# SCH_URM07-Test_2025-05-04.net
KiCad netlist of a schematic drawn in EasyEDA
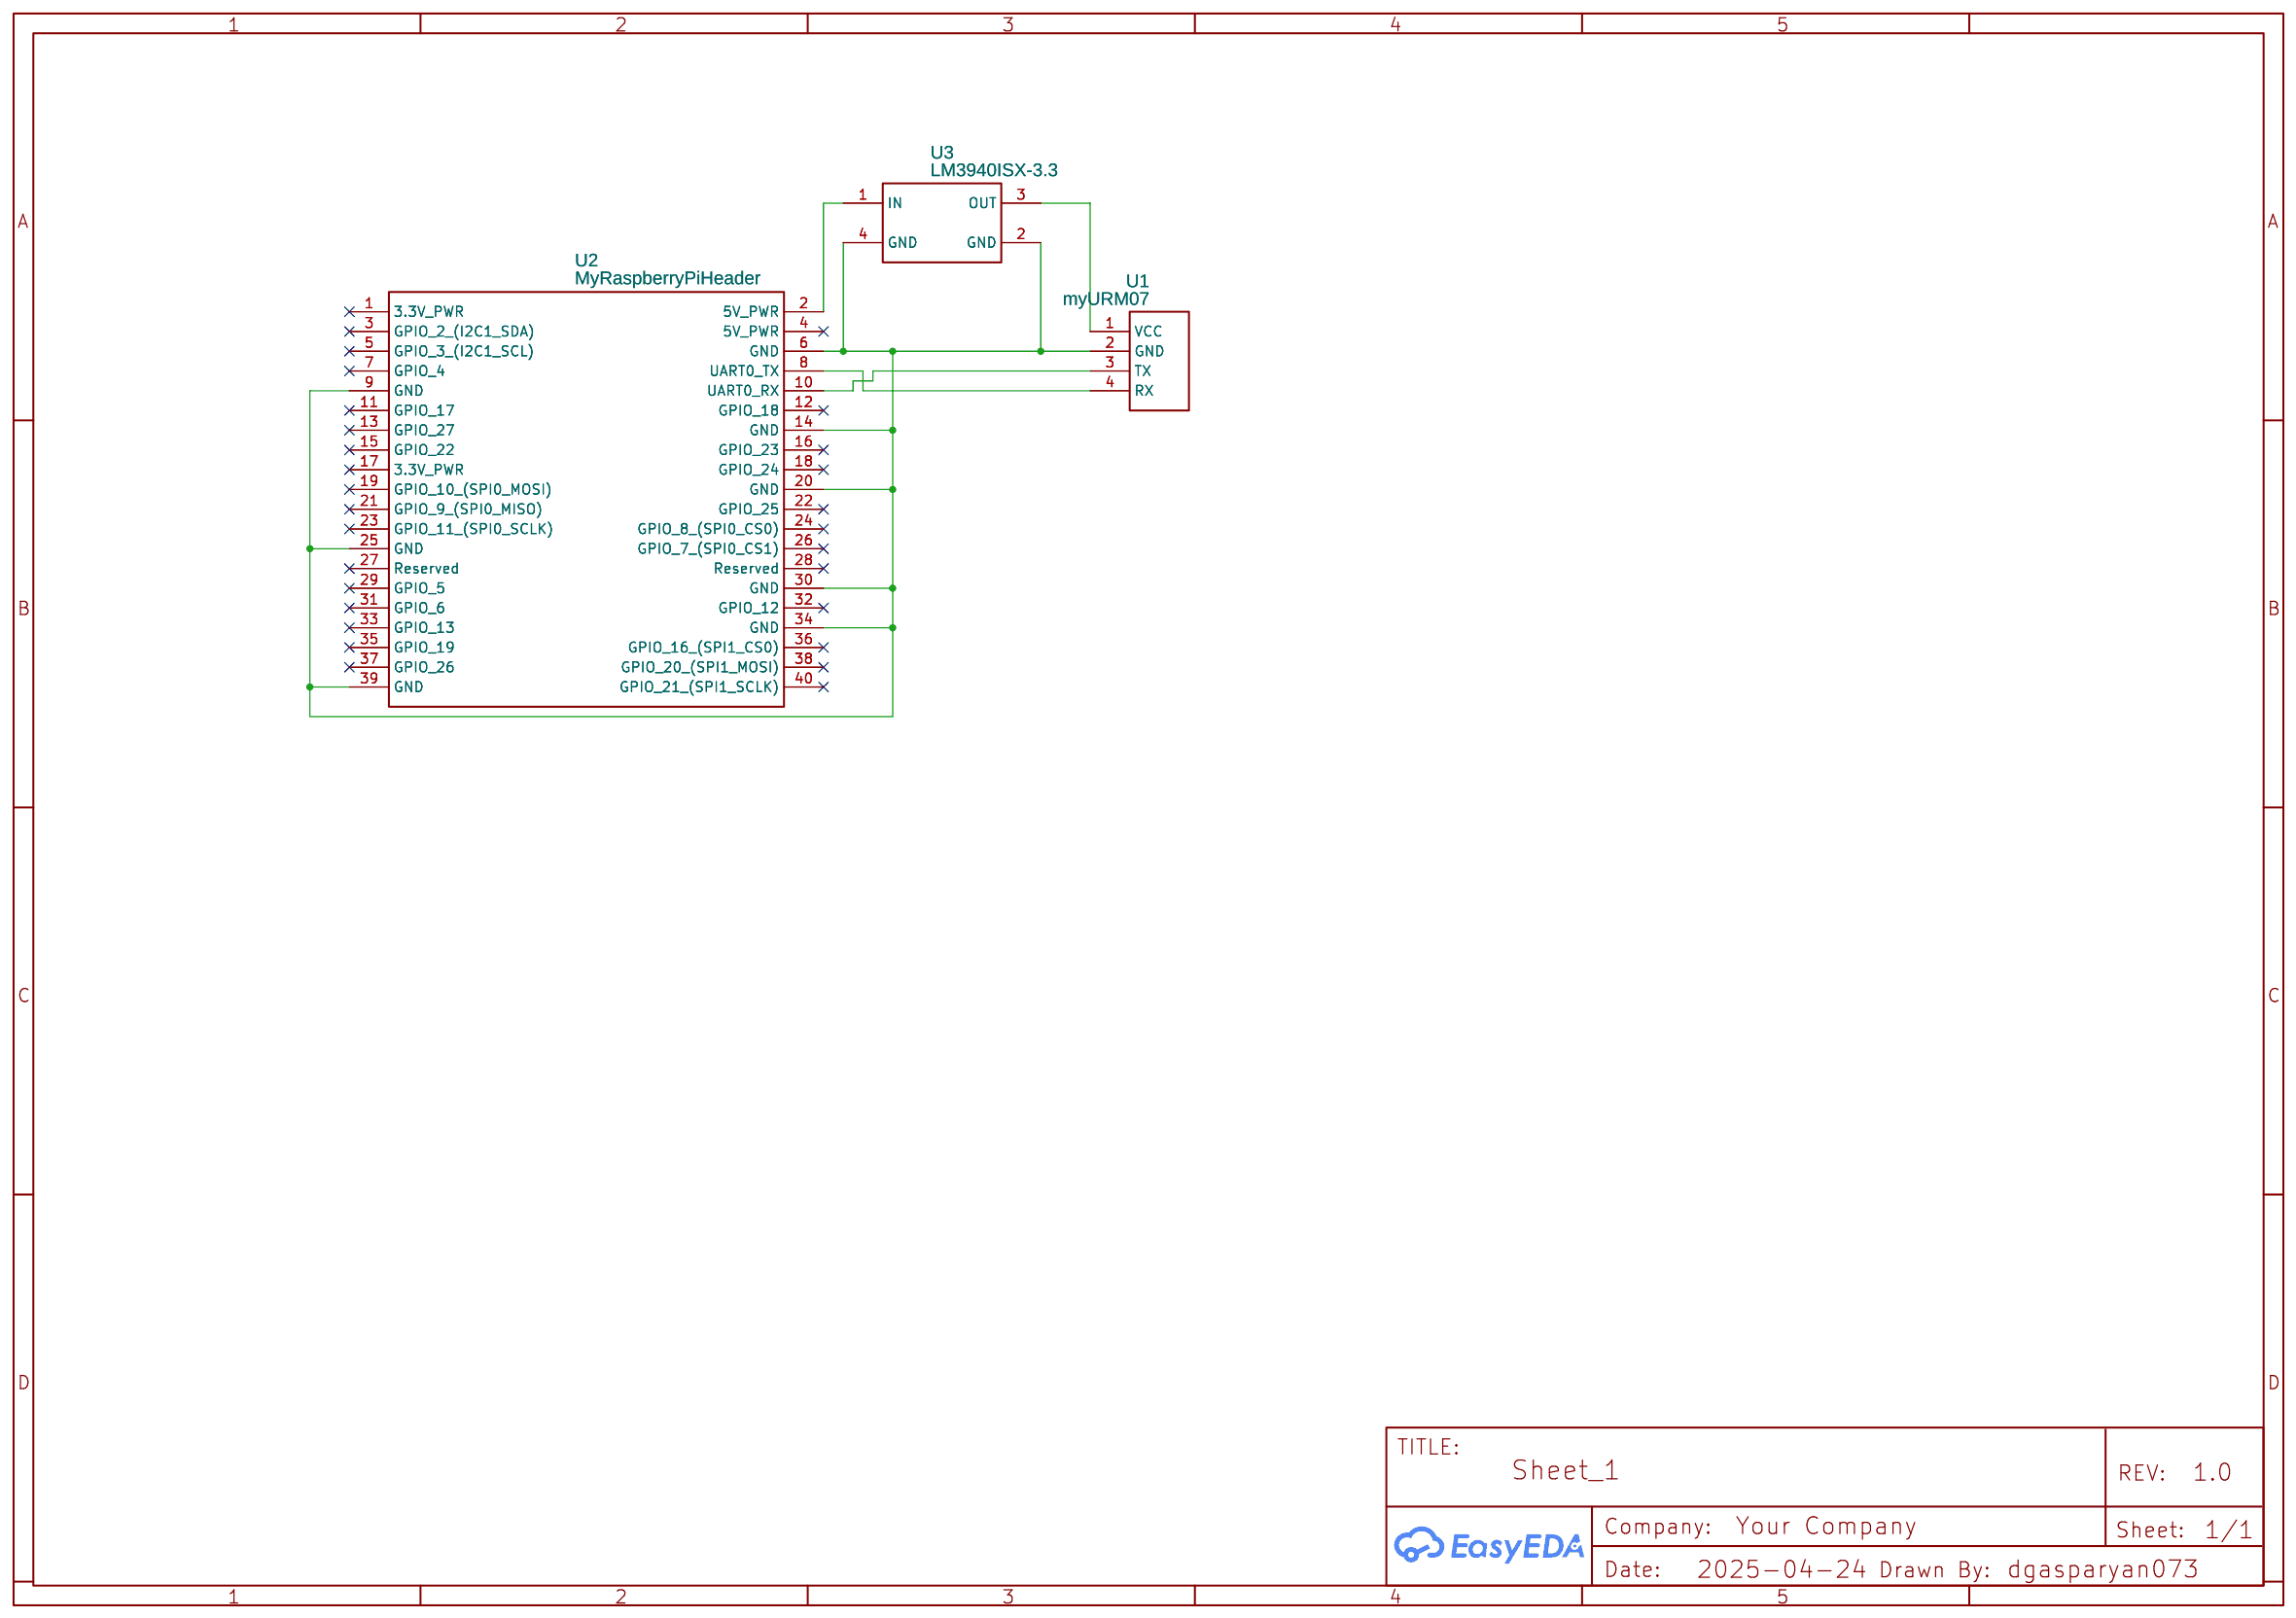
[diagram p0: schematic sheet]

(export (version "E")
  (design (tool "Eeschema 10.0.6"))
  (components
    (comp (ref "U1") (value "myURM07") (libsource (lib "") (part "myURM07")))
    (comp (ref "U2") (value "MyRaspberryPiHeader") (libsource (lib "") (part "MyRaspberryPiHeader")))
    (comp (ref "U3")
      (value "LM3940ISX-3.3")
      (fields
        (field (name "Manufacturer Part") "LM3940ISX-3.3/NOPB")
        (field (name "Manufacturer") "TI(德州仪器)")
      )
      (libsource (lib "") (part "LM3940ISX-3.3"))
    )
  )
  (nets
    (net (code "1") (name "Net-(U1-GND)") (class "Default")
      (node (ref "U1") (pin "2") (pinfunction "GND_2") (pintype "unspecified"))
      (node (ref "U2") (pin "14") (pinfunction "GND_14") (pintype "unspecified"))
      (node (ref "U2") (pin "20") (pinfunction "GND_20") (pintype "unspecified"))
      (node (ref "U2") (pin "25") (pinfunction "GND_25") (pintype "unspecified"))
      (node (ref "U2") (pin "30") (pinfunction "GND_30") (pintype "unspecified"))
      (node (ref "U2") (pin "34") (pinfunction "GND_34") (pintype "unspecified"))
      (node (ref "U2") (pin "39") (pinfunction "GND_39") (pintype "unspecified"))
      (node (ref "U2") (pin "6") (pinfunction "GND_6") (pintype "unspecified"))
      (node (ref "U2") (pin "9") (pinfunction "GND_9") (pintype "unspecified"))
      (node (ref "U3") (pin "2") (pinfunction "GND_2") (pintype "passive"))
      (node (ref "U3") (pin "4") (pinfunction "GND_4") (pintype "passive"))
    )
    (net (code "2") (name "Net-(U1-RX)") (class "Default")
      (node (ref "U1") (pin "4") (pinfunction "RX_4") (pintype "unspecified"))
      (node (ref "U2") (pin "8") (pinfunction "UART0_TX_8") (pintype "unspecified"))
    )
    (net (code "3") (name "Net-(U1-TX)") (class "Default")
      (node (ref "U1") (pin "3") (pinfunction "TX_3") (pintype "unspecified"))
      (node (ref "U2") (pin "10") (pinfunction "UART0_RX_10") (pintype "unspecified"))
    )
    (net (code "4") (name "Net-(U1-VCC)") (class "Default")
      (node (ref "U1") (pin "1") (pinfunction "VCC_1") (pintype "unspecified"))
      (node (ref "U3") (pin "3") (pinfunction "OUT_3") (pintype "passive"))
    )
    (net (code "5") (name "Net-(U3-IN)") (class "Default")
      (node (ref "U2") (pin "2") (pinfunction "5V_PWR_2") (pintype "unspecified"))
      (node (ref "U3") (pin "1") (pinfunction "IN_1") (pintype "passive"))
    )
    (net (code "6") (name "unconnected-(U2-3.3V_PWR-Pad1)") (class "Default")
      (node (ref "U2") (pin "1") (pinfunction "3.3V_PWR_1") (pintype "unspecified+no_connect"))
    )
    (net (code "7") (name "unconnected-(U2-3.3V_PWR-Pad17)") (class "Default")
      (node (ref "U2") (pin "17") (pinfunction "3.3V_PWR_17") (pintype "unspecified+no_connect"))
    )
    (net (code "8") (name "unconnected-(U2-5V_PWR-Pad4)") (class "Default")
      (node (ref "U2") (pin "4") (pinfunction "5V_PWR_4") (pintype "unspecified+no_connect"))
    )
    (net (code "9") (name "unconnected-(U2-GPIO_2_(I2C1_SDA)-Pad3)") (class "Default")
      (node (ref "U2") (pin "3") (pinfunction "GPIO_2_(I2C1_SDA)_3") (pintype "unspecified+no_connect"))
    )
    (net (code "10") (name "unconnected-(U2-GPIO_3_(I2C1_SCL)-Pad5)") (class "Default")
      (node (ref "U2") (pin "5") (pinfunction "GPIO_3_(I2C1_SCL)_5") (pintype "unspecified+no_connect"))
    )
    (net (code "11") (name "unconnected-(U2-GPIO_4-Pad7)") (class "Default")
      (node (ref "U2") (pin "7") (pinfunction "GPIO_4_7") (pintype "unspecified+no_connect"))
    )
    (net (code "12") (name "unconnected-(U2-GPIO_5-Pad29)") (class "Default")
      (node (ref "U2") (pin "29") (pinfunction "GPIO_5_29") (pintype "unspecified+no_connect"))
    )
    (net (code "13") (name "unconnected-(U2-GPIO_6-Pad31)") (class "Default")
      (node (ref "U2") (pin "31") (pinfunction "GPIO_6_31") (pintype "unspecified+no_connect"))
    )
    (net (code "14") (name "unconnected-(U2-GPIO_7_(SPI0_CS1)-Pad26)") (class "Default")
      (node (ref "U2") (pin "26") (pinfunction "GPIO_7_(SPI0_CS1)_26") (pintype "unspecified+no_connect"))
    )
    (net (code "15") (name "unconnected-(U2-GPIO_8_(SPI0_CS0)-Pad24)") (class "Default")
      (node (ref "U2") (pin "24") (pinfunction "GPIO_8_(SPI0_CS0)_24") (pintype "unspecified+no_connect"))
    )
    (net (code "16") (name "unconnected-(U2-GPIO_9_(SPI0_MISO)-Pad21)") (class "Default")
      (node (ref "U2") (pin "21") (pinfunction "GPIO_9_(SPI0_MISO)_21") (pintype "unspecified+no_connect"))
    )
    (net (code "17") (name "unconnected-(U2-GPIO_10_(SPI0_MOSI)-Pad19)") (class "Default")
      (node (ref "U2") (pin "19") (pinfunction "GPIO_10_(SPI0_MOSI)_19") (pintype "unspecified+no_connect"))
    )
    (net (code "18") (name "unconnected-(U2-GPIO_11_(SPI0_SCLK)-Pad23)") (class "Default")
      (node (ref "U2") (pin "23") (pinfunction "GPIO_11_(SPI0_SCLK)_23") (pintype "unspecified+no_connect"))
    )
    (net (code "19") (name "unconnected-(U2-GPIO_12-Pad32)") (class "Default")
      (node (ref "U2") (pin "32") (pinfunction "GPIO_12_32") (pintype "unspecified+no_connect"))
    )
    (net (code "20") (name "unconnected-(U2-GPIO_13-Pad33)") (class "Default")
      (node (ref "U2") (pin "33") (pinfunction "GPIO_13_33") (pintype "unspecified+no_connect"))
    )
    (net (code "21") (name "unconnected-(U2-GPIO_16_(SPI1_CS0)-Pad36)") (class "Default")
      (node (ref "U2") (pin "36") (pinfunction "GPIO_16_(SPI1_CS0)_36") (pintype "unspecified+no_connect"))
    )
    (net (code "22") (name "unconnected-(U2-GPIO_17-Pad11)") (class "Default")
      (node (ref "U2") (pin "11") (pinfunction "GPIO_17_11") (pintype "unspecified+no_connect"))
    )
    (net (code "23") (name "unconnected-(U2-GPIO_18-Pad12)") (class "Default")
      (node (ref "U2") (pin "12") (pinfunction "GPIO_18_12") (pintype "unspecified+no_connect"))
    )
    (net (code "24") (name "unconnected-(U2-GPIO_19-Pad35)") (class "Default")
      (node (ref "U2") (pin "35") (pinfunction "GPIO_19_35") (pintype "unspecified+no_connect"))
    )
    (net (code "25") (name "unconnected-(U2-GPIO_20_(SPI1_MOSI)-Pad38)") (class "Default")
      (node (ref "U2") (pin "38") (pinfunction "GPIO_20_(SPI1_MOSI)_38") (pintype "unspecified+no_connect"))
    )
    (net (code "26") (name "unconnected-(U2-GPIO_21_(SPI1_SCLK)-Pad40)") (class "Default")
      (node (ref "U2") (pin "40") (pinfunction "GPIO_21_(SPI1_SCLK)_40") (pintype "unspecified+no_connect"))
    )
    (net (code "27") (name "unconnected-(U2-GPIO_22-Pad15)") (class "Default")
      (node (ref "U2") (pin "15") (pinfunction "GPIO_22_15") (pintype "unspecified+no_connect"))
    )
    (net (code "28") (name "unconnected-(U2-GPIO_23-Pad16)") (class "Default")
      (node (ref "U2") (pin "16") (pinfunction "GPIO_23_16") (pintype "unspecified+no_connect"))
    )
    (net (code "29") (name "unconnected-(U2-GPIO_24-Pad18)") (class "Default")
      (node (ref "U2") (pin "18") (pinfunction "GPIO_24_18") (pintype "unspecified+no_connect"))
    )
    (net (code "30") (name "unconnected-(U2-GPIO_25-Pad22)") (class "Default")
      (node (ref "U2") (pin "22") (pinfunction "GPIO_25_22") (pintype "unspecified+no_connect"))
    )
    (net (code "31") (name "unconnected-(U2-GPIO_26-Pad37)") (class "Default")
      (node (ref "U2") (pin "37") (pinfunction "GPIO_26_37") (pintype "unspecified+no_connect"))
    )
    (net (code "32") (name "unconnected-(U2-GPIO_27-Pad13)") (class "Default")
      (node (ref "U2") (pin "13") (pinfunction "GPIO_27_13") (pintype "unspecified+no_connect"))
    )
    (net (code "33") (name "unconnected-(U2-Reserved-Pad27)") (class "Default")
      (node (ref "U2") (pin "27") (pinfunction "Reserved_27") (pintype "unspecified+no_connect"))
    )
    (net (code "34") (name "unconnected-(U2-Reserved-Pad28)") (class "Default")
      (node (ref "U2") (pin "28") (pinfunction "Reserved_28") (pintype "unspecified+no_connect"))
    )
  )
)
